# ProtoOne-v1.net
KiCad netlist of a schematic drawn in EAGLE
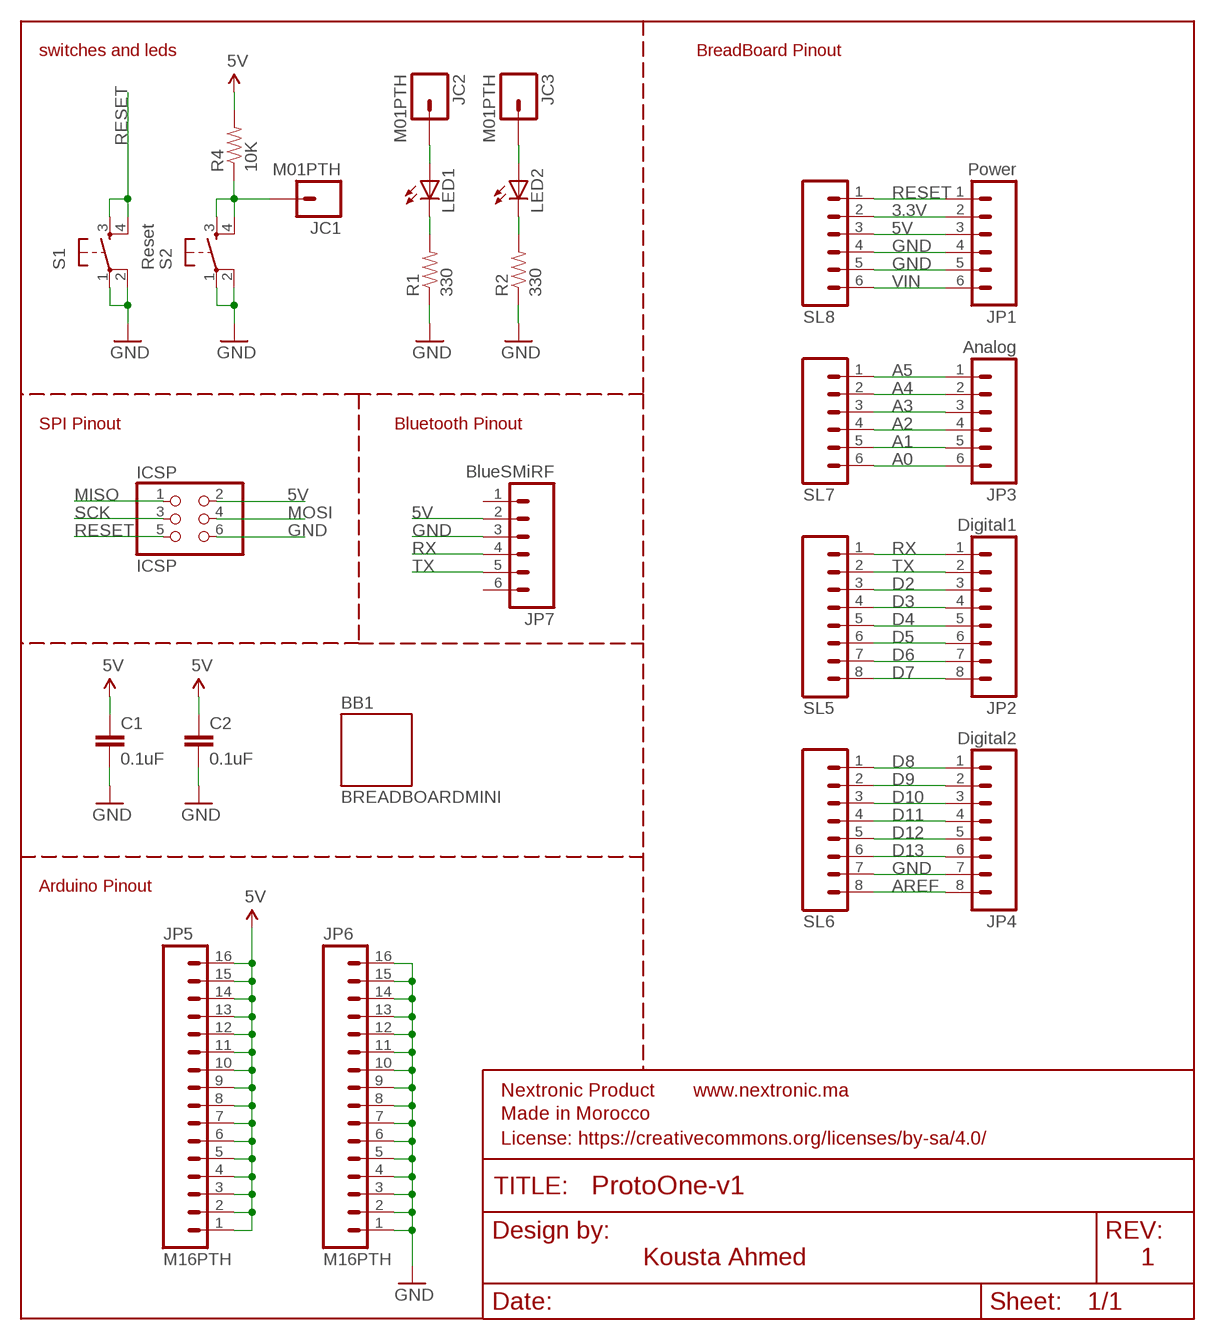
[diagram p0: schematic, sheet 1]

(export (version "E")
  (design (tool "Eeschema 10.0.6"))
  (components
    (comp (ref "BB1")
      (value "BREADBOARDMINI")
      (footprint "eagle-import:BREADBOARD-MINI")
      (libsource (lib "eagle-import") (part "BREADBOARDMINI"))
    )
    (comp (ref "C1")
      (value "0.1uF")
      (footprint "eagle-import:CAP-PTH-SMALL2")
      (fields (field (name "MF") "MULTICOMP") (field (name "MPN") "MC0805B104K500A5.08MM"))
      (libsource (lib "eagle-import") (part "CAPPTH2"))
    )
    (comp (ref "C2")
      (value "0.1uF")
      (footprint "eagle-import:CAP-PTH-SMALL2")
      (fields (field (name "MF") "MULTICOMP") (field (name "MPN") "MC0805B104K500A5.08MM"))
      (libsource (lib "eagle-import") (part "CAPPTH2"))
    )
    (comp (ref "FRAME1")
      (value "FRAME-LETTER")
      (footprint "eagle-import:CREATIVE_COMMONS")
      (fields (field (name "OC_FARNELL") "unknown"))
      (libsource (lib "eagle-import") (part "FRAME-LETTER"))
    )
    (comp (ref "ICSP")
      (value "ICSP")
      (footprint "eagle-import:2X03")
      (libsource (lib "eagle-import") (part "PINHD-2X3"))
    )
    (comp (ref "JC1")
      (value "M01PTH")
      (footprint "eagle-import:1X01")
      (libsource (lib "eagle-import") (part "M01PTH"))
    )
    (comp (ref "JC2")
      (value "M01PTH")
      (footprint "eagle-import:1X01")
      (libsource (lib "eagle-import") (part "M01PTH"))
    )
    (comp (ref "JC3")
      (value "M01PTH")
      (footprint "eagle-import:1X01")
      (libsource (lib "eagle-import") (part "M01PTH"))
    )
    (comp (ref "JP1")
      (value "Power")
      (footprint "eagle-import:1X06")
      (libsource (lib "eagle-import") (part "M06SIP"))
    )
    (comp (ref "JP2")
      (value "Digital1")
      (footprint "eagle-import:1X08")
      (libsource (lib "eagle-import") (part "M08"))
    )
    (comp (ref "JP3")
      (value "Analog")
      (footprint "eagle-import:1X06")
      (libsource (lib "eagle-import") (part "M06SIP"))
    )
    (comp (ref "JP4")
      (value "Digital2")
      (footprint "eagle-import:1X08")
      (libsource (lib "eagle-import") (part "M08"))
    )
    (comp (ref "JP5")
      (value "M16PTH")
      (footprint "eagle-import:1X16")
      (libsource (lib "eagle-import") (part "M16PTH"))
    )
    (comp (ref "JP6")
      (value "M16PTH")
      (footprint "eagle-import:1X16")
      (libsource (lib "eagle-import") (part "M16PTH"))
    )
    (comp (ref "JP7")
      (value "BlueSMiRF")
      (footprint "eagle-import:1X06")
      (libsource (lib "eagle-import") (part "M06SIP"))
    )
    (comp (ref "LED1")
      (value "LED5MM")
      (footprint "eagle-import:LED5MM")
      (libsource (lib "eagle-import") (part "LED5MM"))
    )
    (comp (ref "LED2")
      (value "LED5MM")
      (footprint "eagle-import:LED5MM")
      (libsource (lib "eagle-import") (part "LED5MM"))
    )
    (comp (ref "R1")
      (value "330")
      (footprint "eagle-import:AXIAL-0.3")
      (libsource (lib "eagle-import") (part "RESISTORPTH1"))
    )
    (comp (ref "R2")
      (value "330")
      (footprint "eagle-import:AXIAL-0.3")
      (libsource (lib "eagle-import") (part "RESISTORPTH1"))
    )
    (comp (ref "R4")
      (value "10K")
      (footprint "eagle-import:AXIAL-0.3")
      (fields (field (name "MF") "SUSUMU") (field (name "MPN") "RR0816P-103-B-T5"))
      (libsource (lib "eagle-import") (part "RESISTORPTH1"))
    )
    (comp (ref "S1")
      (value "Reset")
      (footprint "eagle-import:TACTILE-PTH")
      (libsource (lib "eagle-import") (part "TAC_SWITCHPTH"))
    )
    (comp (ref "S2")
      (value "TAC_SWITCHPTH")
      (footprint "eagle-import:TACTILE-PTH")
      (libsource (lib "eagle-import") (part "TAC_SWITCHPTH"))
    )
    (comp (ref "SL5")
      (value "M08")
      (footprint "eagle-import:1X08")
      (libsource (lib "eagle-import") (part "M08"))
    )
    (comp (ref "SL6")
      (value "M08")
      (footprint "eagle-import:1X08")
      (libsource (lib "eagle-import") (part "M08"))
    )
    (comp (ref "SL7")
      (value "M06SIP")
      (footprint "eagle-import:1X06")
      (libsource (lib "eagle-import") (part "M06SIP"))
    )
    (comp (ref "SL8")
      (value "M06SIP")
      (footprint "eagle-import:1X06")
      (libsource (lib "eagle-import") (part "M06SIP"))
    )
  )
  (nets
    (net (code "1") (name "/3.3V") (class "Default")
      (node (ref "JP1") (pin "2") (pinfunction "2_2") (pintype "passive"))
      (node (ref "SL8") (pin "2") (pinfunction "2_2") (pintype "passive"))
    )
    (net (code "2") (name "/A0") (class "Default")
      (node (ref "JP3") (pin "6") (pinfunction "6_6") (pintype "passive"))
      (node (ref "SL7") (pin "6") (pinfunction "6_6") (pintype "passive"))
    )
    (net (code "3") (name "/A1") (class "Default")
      (node (ref "JP3") (pin "5") (pinfunction "5_5") (pintype "passive"))
      (node (ref "SL7") (pin "5") (pinfunction "5_5") (pintype "passive"))
    )
    (net (code "4") (name "/A2") (class "Default")
      (node (ref "JP3") (pin "4") (pinfunction "4_4") (pintype "passive"))
      (node (ref "SL7") (pin "4") (pinfunction "4_4") (pintype "passive"))
    )
    (net (code "5") (name "/A3") (class "Default")
      (node (ref "JP3") (pin "3") (pinfunction "3_3") (pintype "passive"))
      (node (ref "SL7") (pin "3") (pinfunction "3_3") (pintype "passive"))
    )
    (net (code "6") (name "/A4") (class "Default")
      (node (ref "JP3") (pin "2") (pinfunction "2_2") (pintype "passive"))
      (node (ref "SL7") (pin "2") (pinfunction "2_2") (pintype "passive"))
    )
    (net (code "7") (name "/A5") (class "Default")
      (node (ref "JP3") (pin "1") (pinfunction "1_1") (pintype "passive"))
      (node (ref "SL7") (pin "1") (pinfunction "1_1") (pintype "passive"))
    )
    (net (code "8") (name "/AREF") (class "Default")
      (node (ref "JP4") (pin "8") (pinfunction "8_8") (pintype "passive"))
      (node (ref "SL6") (pin "8") (pinfunction "8_8") (pintype "passive"))
    )
    (net (code "9") (name "/D2") (class "Default")
      (node (ref "JP2") (pin "3") (pinfunction "3_3") (pintype "passive"))
      (node (ref "SL5") (pin "3") (pinfunction "3_3") (pintype "passive"))
    )
    (net (code "10") (name "/D3") (class "Default")
      (node (ref "JP2") (pin "4") (pinfunction "4_4") (pintype "passive"))
      (node (ref "SL5") (pin "4") (pinfunction "4_4") (pintype "passive"))
    )
    (net (code "11") (name "/D4") (class "Default")
      (node (ref "JP2") (pin "5") (pinfunction "5_5") (pintype "passive"))
      (node (ref "SL5") (pin "5") (pinfunction "5_5") (pintype "passive"))
    )
    (net (code "12") (name "/D5") (class "Default")
      (node (ref "JP2") (pin "6") (pinfunction "6_6") (pintype "passive"))
      (node (ref "SL5") (pin "6") (pinfunction "6_6") (pintype "passive"))
    )
    (net (code "13") (name "/D6") (class "Default")
      (node (ref "JP2") (pin "7") (pinfunction "7_7") (pintype "passive"))
      (node (ref "SL5") (pin "7") (pinfunction "7_7") (pintype "passive"))
    )
    (net (code "14") (name "/D7") (class "Default")
      (node (ref "JP2") (pin "8") (pinfunction "8_8") (pintype "passive"))
      (node (ref "SL5") (pin "8") (pinfunction "8_8") (pintype "passive"))
    )
    (net (code "15") (name "/D8") (class "Default")
      (node (ref "JP4") (pin "1") (pinfunction "1_1") (pintype "passive"))
      (node (ref "SL6") (pin "1") (pinfunction "1_1") (pintype "passive"))
    )
    (net (code "16") (name "/D9") (class "Default")
      (node (ref "JP4") (pin "2") (pinfunction "2_2") (pintype "passive"))
      (node (ref "SL6") (pin "2") (pinfunction "2_2") (pintype "passive"))
    )
    (net (code "17") (name "/D10") (class "Default")
      (node (ref "JP4") (pin "3") (pinfunction "3_3") (pintype "passive"))
      (node (ref "SL6") (pin "3") (pinfunction "3_3") (pintype "passive"))
    )
    (net (code "18") (name "/D11") (class "Default")
      (node (ref "JP4") (pin "4") (pinfunction "4_4") (pintype "passive"))
      (node (ref "SL6") (pin "4") (pinfunction "4_4") (pintype "passive"))
    )
    (net (code "19") (name "/D12") (class "Default")
      (node (ref "JP4") (pin "5") (pinfunction "5_5") (pintype "passive"))
      (node (ref "SL6") (pin "5") (pinfunction "5_5") (pintype "passive"))
    )
    (net (code "20") (name "/D13") (class "Default")
      (node (ref "JP4") (pin "6") (pinfunction "6_6") (pintype "passive"))
      (node (ref "SL6") (pin "6") (pinfunction "6_6") (pintype "passive"))
    )
    (net (code "21") (name "/MISO") (class "Default")
      (node (ref "ICSP") (pin "1") (pinfunction "1_1") (pintype "passive"))
    )
    (net (code "22") (name "/MOSI") (class "Default")
      (node (ref "ICSP") (pin "4") (pinfunction "4_4") (pintype "passive"))
    )
    (net (code "23") (name "/RESET") (class "Default")
      (node (ref "ICSP") (pin "5") (pinfunction "5_5") (pintype "passive"))
      (node (ref "JP1") (pin "1") (pinfunction "1_1") (pintype "passive"))
      (node (ref "S1") (pin "3") (pinfunction "3_3") (pintype "passive"))
      (node (ref "S1") (pin "4") (pinfunction "4_4") (pintype "passive"))
      (node (ref "SL8") (pin "1") (pinfunction "1_1") (pintype "passive"))
    )
    (net (code "24") (name "/RX") (class "Default")
      (node (ref "JP2") (pin "1") (pinfunction "1_1") (pintype "passive"))
      (node (ref "JP7") (pin "4") (pinfunction "4_4") (pintype "passive"))
      (node (ref "SL5") (pin "1") (pinfunction "1_1") (pintype "passive"))
    )
    (net (code "25") (name "/SCK") (class "Default")
      (node (ref "ICSP") (pin "3") (pinfunction "3_3") (pintype "passive"))
    )
    (net (code "26") (name "/TX") (class "Default")
      (node (ref "JP2") (pin "2") (pinfunction "2_2") (pintype "passive"))
      (node (ref "JP7") (pin "5") (pinfunction "5_5") (pintype "passive"))
      (node (ref "SL5") (pin "2") (pinfunction "2_2") (pintype "passive"))
    )
    (net (code "27") (name "/VIN") (class "Default")
      (node (ref "JP1") (pin "6") (pinfunction "6_6") (pintype "passive"))
      (node (ref "SL8") (pin "6") (pinfunction "6_6") (pintype "passive"))
    )
    (net (code "28") (name "5V") (class "Default")
      (node (ref "C1") (pin "1") (pinfunction "1_1") (pintype "passive"))
      (node (ref "C2") (pin "1") (pinfunction "1_1") (pintype "passive"))
      (node (ref "ICSP") (pin "2") (pinfunction "2_2") (pintype "passive"))
      (node (ref "JP1") (pin "3") (pinfunction "3_3") (pintype "passive"))
      (node (ref "JP5") (pin "1") (pinfunction "1_1") (pintype "passive"))
      (node (ref "JP5") (pin "10") (pinfunction "10_10") (pintype "passive"))
      (node (ref "JP5") (pin "11") (pinfunction "11_11") (pintype "passive"))
      (node (ref "JP5") (pin "12") (pinfunction "12_12") (pintype "passive"))
      (node (ref "JP5") (pin "13") (pinfunction "13_13") (pintype "passive"))
      (node (ref "JP5") (pin "14") (pinfunction "14_14") (pintype "passive"))
      (node (ref "JP5") (pin "15") (pinfunction "15_15") (pintype "passive"))
      (node (ref "JP5") (pin "16") (pinfunction "16_16") (pintype "passive"))
      (node (ref "JP5") (pin "2") (pinfunction "2_2") (pintype "passive"))
      (node (ref "JP5") (pin "3") (pinfunction "3_3") (pintype "passive"))
      (node (ref "JP5") (pin "4") (pinfunction "4_4") (pintype "passive"))
      (node (ref "JP5") (pin "5") (pinfunction "5_5") (pintype "passive"))
      (node (ref "JP5") (pin "6") (pinfunction "6_6") (pintype "passive"))
      (node (ref "JP5") (pin "7") (pinfunction "7_7") (pintype "passive"))
      (node (ref "JP5") (pin "8") (pinfunction "8_8") (pintype "passive"))
      (node (ref "JP5") (pin "9") (pinfunction "9_9") (pintype "passive"))
      (node (ref "JP7") (pin "2") (pinfunction "2_2") (pintype "passive"))
      (node (ref "R4") (pin "P$2") (pinfunction "2_P$2") (pintype "passive"))
      (node (ref "SL8") (pin "3") (pinfunction "3_3") (pintype "passive"))
    )
    (net (code "29") (name "GND") (class "Default")
      (node (ref "C1") (pin "2") (pinfunction "2_2") (pintype "passive"))
      (node (ref "C2") (pin "2") (pinfunction "2_2") (pintype "passive"))
      (node (ref "ICSP") (pin "6") (pinfunction "6_6") (pintype "passive"))
      (node (ref "JP1") (pin "4") (pinfunction "4_4") (pintype "passive"))
      (node (ref "JP1") (pin "5") (pinfunction "5_5") (pintype "passive"))
      (node (ref "JP4") (pin "7") (pinfunction "7_7") (pintype "passive"))
      (node (ref "JP6") (pin "1") (pinfunction "1_1") (pintype "passive"))
      (node (ref "JP6") (pin "10") (pinfunction "10_10") (pintype "passive"))
      (node (ref "JP6") (pin "11") (pinfunction "11_11") (pintype "passive"))
      (node (ref "JP6") (pin "12") (pinfunction "12_12") (pintype "passive"))
      (node (ref "JP6") (pin "13") (pinfunction "13_13") (pintype "passive"))
      (node (ref "JP6") (pin "14") (pinfunction "14_14") (pintype "passive"))
      (node (ref "JP6") (pin "15") (pinfunction "15_15") (pintype "passive"))
      (node (ref "JP6") (pin "16") (pinfunction "16_16") (pintype "passive"))
      (node (ref "JP6") (pin "2") (pinfunction "2_2") (pintype "passive"))
      (node (ref "JP6") (pin "3") (pinfunction "3_3") (pintype "passive"))
      (node (ref "JP6") (pin "4") (pinfunction "4_4") (pintype "passive"))
      (node (ref "JP6") (pin "5") (pinfunction "5_5") (pintype "passive"))
      (node (ref "JP6") (pin "6") (pinfunction "6_6") (pintype "passive"))
      (node (ref "JP6") (pin "7") (pinfunction "7_7") (pintype "passive"))
      (node (ref "JP6") (pin "8") (pinfunction "8_8") (pintype "passive"))
      (node (ref "JP6") (pin "9") (pinfunction "9_9") (pintype "passive"))
      (node (ref "JP7") (pin "3") (pinfunction "3_3") (pintype "passive"))
      (node (ref "R1") (pin "P$1") (pinfunction "1_P$1") (pintype "passive"))
      (node (ref "R2") (pin "P$1") (pinfunction "1_P$1") (pintype "passive"))
      (node (ref "S1") (pin "1") (pinfunction "1_1") (pintype "passive"))
      (node (ref "S1") (pin "2") (pinfunction "2_2") (pintype "passive"))
      (node (ref "S2") (pin "1") (pinfunction "1_1") (pintype "passive"))
      (node (ref "S2") (pin "2") (pinfunction "2_2") (pintype "passive"))
      (node (ref "SL6") (pin "7") (pinfunction "7_7") (pintype "passive"))
      (node (ref "SL8") (pin "4") (pinfunction "4_4") (pintype "passive"))
      (node (ref "SL8") (pin "5") (pinfunction "5_5") (pintype "passive"))
    )
    (net (code "30") (name "Net-(JC2-Pad1)") (class "Default")
      (node (ref "JC2") (pin "1") (pinfunction "1_1") (pintype "passive"))
      (node (ref "LED1") (pin "A") (pinfunction "A_A") (pintype "passive"))
    )
    (net (code "31") (name "Net-(JC3-Pad1)") (class "Default")
      (node (ref "JC3") (pin "1") (pinfunction "1_1") (pintype "passive"))
      (node (ref "LED2") (pin "A") (pinfunction "A_A") (pintype "passive"))
    )
    (net (code "32") (name "Net-(LED1-C)") (class "Default")
      (node (ref "LED1") (pin "K") (pinfunction "C_K") (pintype "passive"))
      (node (ref "R1") (pin "P$2") (pinfunction "2_P$2") (pintype "passive"))
    )
    (net (code "33") (name "Net-(LED2-C)") (class "Default")
      (node (ref "LED2") (pin "K") (pinfunction "C_K") (pintype "passive"))
      (node (ref "R2") (pin "P$2") (pinfunction "2_P$2") (pintype "passive"))
    )
    (net (code "34") (name "Net-(R4-1)") (class "Default")
      (node (ref "JC1") (pin "1") (pinfunction "1_1") (pintype "passive"))
      (node (ref "R4") (pin "P$1") (pinfunction "1_P$1") (pintype "passive"))
      (node (ref "S2") (pin "3") (pinfunction "3_3") (pintype "passive"))
      (node (ref "S2") (pin "4") (pinfunction "4_4") (pintype "passive"))
    )
    (net (code "35") (name "unconnected-(JP7-Pad1)") (class "Default")
      (node (ref "JP7") (pin "1") (pinfunction "1_1") (pintype "passive"))
    )
    (net (code "36") (name "unconnected-(JP7-Pad6)") (class "Default")
      (node (ref "JP7") (pin "6") (pinfunction "6_6") (pintype "passive"))
    )
  )
)
